# Filter.net
KiCad netlist of a schematic drawn in Altium Designer
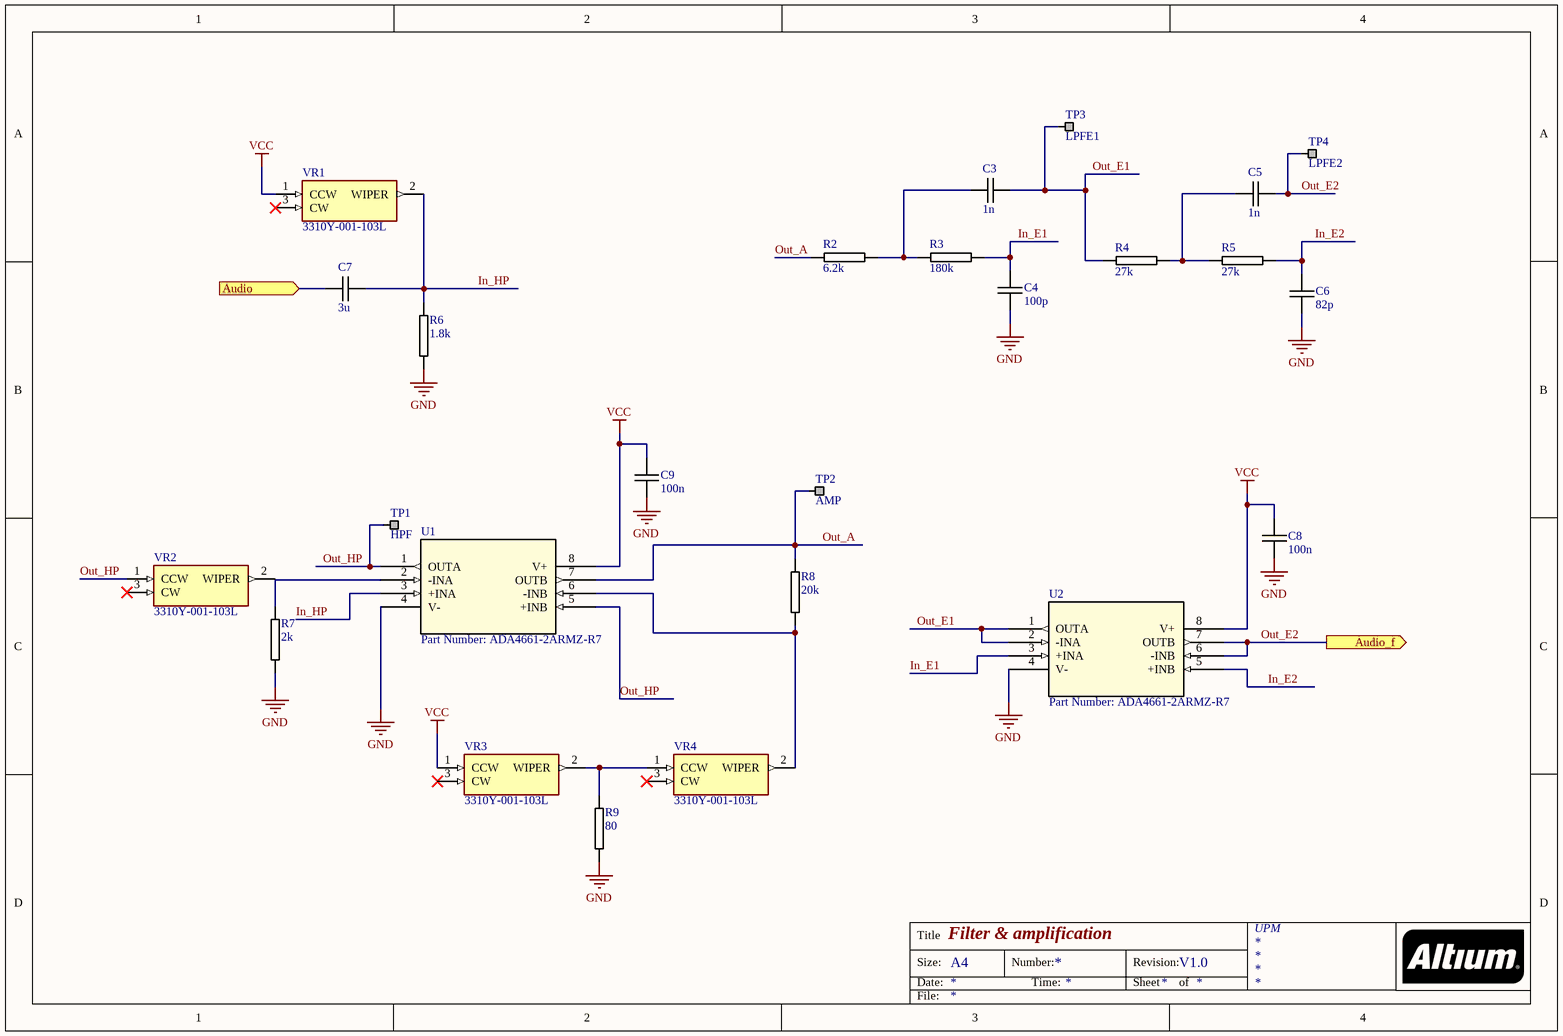
[diagram p0: Filter.SchDoc]

(export (version "E")
  (design (tool "Eeschema 10.0.6"))
  (components
    (comp (ref "C3")
      (value "1n")
      (footprint "0805C-GENERIC")
      (description "GENERIC CAPACITOR NON POLARISED0603")
      (libsource (lib "vh_altium_library") (part "C0805-GENERIC"))
    )
    (comp (ref "C4")
      (value "100p")
      (footprint "0805C-GENERIC")
      (description "GENERIC CAPACITOR NON POLARISED0603")
      (libsource (lib "vh_altium_library") (part "C0805-GENERIC"))
    )
    (comp (ref "C5")
      (value "1n")
      (footprint "0805C-GENERIC")
      (description "GENERIC CAPACITOR NON POLARISED0603")
      (libsource (lib "vh_altium_library") (part "C0805-GENERIC"))
    )
    (comp (ref "C6")
      (value "82p")
      (footprint "0805C-GENERIC")
      (description "GENERIC CAPACITOR NON POLARISED0603")
      (libsource (lib "vh_altium_library") (part "C0805-GENERIC"))
    )
    (comp (ref "C7")
      (value "3u")
      (footprint "0805C-GENERIC")
      (description "GENERIC CAPACITOR NON POLARISED0603")
      (libsource (lib "vh_altium_library") (part "C0805-GENERIC"))
    )
    (comp (ref "C8")
      (value "100n")
      (footprint "0805C-GENERIC")
      (description "GENERIC CAPACITOR NON POLARISED0603")
      (libsource (lib "vh_altium_library") (part "C0805-GENERIC"))
    )
    (comp (ref "C9")
      (value "100n")
      (footprint "0805C-GENERIC")
      (description "GENERIC CAPACITOR NON POLARISED0603")
      (libsource (lib "vh_altium_library") (part "C0805-GENERIC"))
    )
    (comp (ref "R2")
      (value "6.2k")
      (footprint "0805R-GENERIC")
      (description "GENERIC RESISTOR 0805")
      (libsource (lib "vh_altium_library") (part "R0805-GENERIC"))
    )
    (comp (ref "R3")
      (value "180k")
      (footprint "0805R-GENERIC")
      (description "GENERIC RESISTOR 0805")
      (libsource (lib "vh_altium_library") (part "R0805-GENERIC"))
    )
    (comp (ref "R4")
      (value "27k")
      (footprint "0805R-GENERIC")
      (description "GENERIC RESISTOR 0805")
      (libsource (lib "vh_altium_library") (part "R0805-GENERIC"))
    )
    (comp (ref "R5")
      (value "27k")
      (footprint "0805R-GENERIC")
      (description "GENERIC RESISTOR 0805")
      (libsource (lib "vh_altium_library") (part "R0805-GENERIC"))
    )
    (comp (ref "R6")
      (value "1.8k")
      (footprint "0805R-GENERIC")
      (description "GENERIC RESISTOR 0805")
      (libsource (lib "vh_altium_library") (part "R0805-GENERIC"))
    )
    (comp (ref "R7")
      (value "2k")
      (footprint "0805R-GENERIC")
      (description "GENERIC RESISTOR 0805")
      (libsource (lib "vh_altium_library") (part "R0805-GENERIC"))
    )
    (comp (ref "R8")
      (value "20k")
      (footprint "0805R-GENERIC")
      (description "GENERIC RESISTOR 0805")
      (libsource (lib "vh_altium_library") (part "R0805-GENERIC"))
    )
    (comp (ref "R9")
      (value "80")
      (footprint "0805R-GENERIC")
      (description "GENERIC RESISTOR 0805")
      (libsource (lib "vh_altium_library") (part "R0805-GENERIC"))
    )
    (comp (ref "TP1")
      (value "HPF")
      (footprint "TESTPIN")
      (description "TESTPIN SINGLE PIN HEADER")
      (libsource (lib "vh_altium_library") (part "TESTPIN"))
    )
    (comp (ref "TP2")
      (value "AMP")
      (footprint "TESTPIN")
      (description "TESTPIN SINGLE PIN HEADER")
      (libsource (lib "vh_altium_library") (part "TESTPIN"))
    )
    (comp (ref "TP3")
      (value "LPFE1")
      (footprint "TESTPIN")
      (description "TESTPIN SINGLE PIN HEADER")
      (libsource (lib "vh_altium_library") (part "TESTPIN"))
    )
    (comp (ref "TP4")
      (value "LPFE2")
      (footprint "TESTPIN")
      (description "TESTPIN SINGLE PIN HEADER")
      (libsource (lib "vh_altium_library") (part "TESTPIN"))
    )
    (comp (ref "U1")
      (value "Part Number: ADA4661-2ARMZ-R7")
      (footprint "RM_8")
      (description "No Description Available")
      (fields
        (field (name "MANUFACTURER_PART_NUMBER") "ADA4661-2ARMZ-R7")
        (field (name "COPYRIGHT") "Copyright (C) 2016 Accelerated Designs. All rights reserved")
      )
      (libsource (lib "2020-03-25_06-16-48") (part "ADA4661-2ARMZ-R7"))
    )
    (comp (ref "U2")
      (value "Part Number: ADA4661-2ARMZ-R7")
      (footprint "RM_8")
      (description "No Description Available")
      (fields
        (field (name "MANUFACTURER_PART_NUMBER") "ADA4661-2ARMZ-R7")
        (field (name "COPYRIGHT") "Copyright (C) 2016 Accelerated Designs. All rights reserved")
      )
      (libsource (lib "2020-03-25_06-16-48") (part "ADA4661-2ARMZ-R7"))
    )
    (comp (ref "VR1")
      (value "3310Y-001-103L")
      (footprint "3310Y-001")
      (description "Variable Resistor")
      (fields
        (field (name "MOUSER PART NUMBER") "652-3310Y-001-103L")
        (field (name "RS PART NUMBER") "5220625P")
      )
      (libsource (lib "PMOD") (part "3310Y-001-103L"))
    )
    (comp (ref "VR2")
      (value "3310Y-001-103L")
      (footprint "3310Y-001")
      (description "Variable Resistor")
      (fields
        (field (name "MOUSER PART NUMBER") "652-3310Y-001-103L")
        (field (name "RS PART NUMBER") "5220625P")
      )
      (libsource (lib "PMOD") (part "3310Y-001-103L"))
    )
    (comp (ref "VR3")
      (value "3310Y-001-103L")
      (footprint "3310Y-001")
      (description "Variable Resistor")
      (fields
        (field (name "MOUSER PART NUMBER") "652-3310Y-001-103L")
        (field (name "RS PART NUMBER") "5220625P")
      )
      (libsource (lib "PMOD") (part "3310Y-001-103L"))
    )
    (comp (ref "VR4")
      (value "3310Y-001-103L")
      (footprint "3310Y-001")
      (description "Variable Resistor")
      (fields
        (field (name "MOUSER PART NUMBER") "652-3310Y-001-103L")
        (field (name "RS PART NUMBER") "5220625P")
      )
      (libsource (lib "PMOD") (part "3310Y-001-103L"))
    )
  )
  (nets
    (net (code "1") (name "/Audio") (class "Default") (node (ref "C7") (pin "1") (pintype "passive")))
    (net (code "2") (name "/In_E1") (class "Default")
      (node (ref "C4") (pin "2") (pintype "passive"))
      (node (ref "R3") (pin "2") (pintype "passive"))
      (node (ref "U2") (pin "3") (pinfunction "+INA_3") (pintype "input"))
    )
    (net (code "3") (name "/In_E2") (class "Default")
      (node (ref "C6") (pin "2") (pintype "passive"))
      (node (ref "R5") (pin "2") (pintype "passive"))
      (node (ref "U2") (pin "5") (pinfunction "+INB_5") (pintype "input"))
    )
    (net (code "4") (name "/In_HP") (class "Default")
      (node (ref "C7") (pin "2") (pintype "passive"))
      (node (ref "R6") (pin "1") (pintype "passive"))
      (node (ref "U1") (pin "3") (pinfunction "+INA_3") (pintype "input"))
      (node (ref "VR1") (pin "2") (pinfunction "WIPER_2") (pintype "output"))
    )
    (net (code "5") (name "/Out_A") (class "Default")
      (node (ref "R2") (pin "1") (pintype "passive"))
      (node (ref "R8") (pin "1") (pintype "passive"))
      (node (ref "TP2") (pin "1") (pinfunction "1_1") (pintype "passive"))
      (node (ref "U1") (pin "7") (pinfunction "OUTB_7") (pintype "output"))
    )
    (net (code "6") (name "/Out_E1") (class "Default")
      (node (ref "C3") (pin "2") (pintype "passive"))
      (node (ref "R4") (pin "1") (pintype "passive"))
      (node (ref "TP3") (pin "1") (pinfunction "1_1") (pintype "passive"))
      (node (ref "U2") (pin "1") (pinfunction "OUTA_1") (pintype "output"))
      (node (ref "U2") (pin "2") (pinfunction "-INA_2") (pintype "input"))
    )
    (net (code "7") (name "/Out_E2") (class "Default")
      (node (ref "C5") (pin "2") (pintype "passive"))
      (node (ref "TP4") (pin "1") (pinfunction "1_1") (pintype "passive"))
      (node (ref "U2") (pin "6") (pinfunction "-INB_6") (pintype "input"))
      (node (ref "U2") (pin "7") (pinfunction "OUTB_7") (pintype "output"))
    )
    (net (code "8") (name "/Out_HP") (class "Default")
      (node (ref "TP1") (pin "1") (pinfunction "1_1") (pintype "passive"))
      (node (ref "U1") (pin "1") (pinfunction "OUTA_1") (pintype "output"))
      (node (ref "U1") (pin "5") (pinfunction "+INB_5") (pintype "input"))
      (node (ref "VR2") (pin "1") (pinfunction "CCW_1") (pintype "input"))
    )
    (net (code "9") (name "GND") (class "Default")
      (node (ref "C4") (pin "1") (pintype "passive"))
      (node (ref "C6") (pin "1") (pintype "passive"))
      (node (ref "C8") (pin "2") (pintype "passive"))
      (node (ref "C9") (pin "2") (pintype "passive"))
      (node (ref "R6") (pin "2") (pintype "passive"))
      (node (ref "R7") (pin "2") (pintype "passive"))
      (node (ref "R9") (pin "2") (pintype "passive"))
      (node (ref "U1") (pin "4") (pinfunction "V-_4") (pintype "power_in"))
      (node (ref "U2") (pin "4") (pinfunction "V-_4") (pintype "power_in"))
    )
    (net (code "10") (name "Net-(C3-Pad1)") (class "Default")
      (node (ref "C3") (pin "1") (pintype "passive"))
      (node (ref "R2") (pin "2") (pintype "passive"))
      (node (ref "R3") (pin "1") (pintype "passive"))
    )
    (net (code "11") (name "Net-(C5-Pad1)") (class "Default")
      (node (ref "C5") (pin "1") (pintype "passive"))
      (node (ref "R4") (pin "2") (pintype "passive"))
      (node (ref "R5") (pin "1") (pintype "passive"))
    )
    (net (code "12") (name "Net-(U1--INA)") (class "Default")
      (node (ref "R7") (pin "1") (pintype "passive"))
      (node (ref "U1") (pin "2") (pinfunction "-INA_2") (pintype "input"))
    )
    (net (code "13") (name "Net-(U1--INB)") (class "Default")
      (node (ref "R8") (pin "2") (pintype "passive"))
      (node (ref "U1") (pin "6") (pinfunction "-INB_6") (pintype "input"))
      (node (ref "VR4") (pin "2") (pinfunction "WIPER_2") (pintype "output"))
    )
    (net (code "14") (name "Net-(VR3-WIPER)") (class "Default")
      (node (ref "R9") (pin "1") (pintype "passive"))
      (node (ref "VR3") (pin "2") (pinfunction "WIPER_2") (pintype "output"))
      (node (ref "VR4") (pin "1") (pinfunction "CCW_1") (pintype "input"))
    )
    (net (code "15") (name "VCC") (class "Default")
      (node (ref "C8") (pin "1") (pintype "passive"))
      (node (ref "C9") (pin "1") (pintype "passive"))
      (node (ref "U1") (pin "8") (pinfunction "V+_8") (pintype "power_in"))
      (node (ref "U2") (pin "8") (pinfunction "V+_8") (pintype "power_in"))
      (node (ref "VR1") (pin "1") (pinfunction "CCW_1") (pintype "input"))
      (node (ref "VR3") (pin "1") (pinfunction "CCW_1") (pintype "input"))
    )
    (net (code "16") (name "unconnected-(VR1-CW-Pad3)") (class "Default")
      (node (ref "VR1") (pin "3") (pinfunction "CW_3") (pintype "input+no_connect"))
    )
    (net (code "17") (name "unconnected-(VR2-CW-Pad3)") (class "Default")
      (node (ref "VR2") (pin "3") (pinfunction "CW_3") (pintype "input+no_connect"))
    )
    (net (code "18") (name "unconnected-(VR2-WIPER-Pad2)") (class "Default")
      (node (ref "VR2") (pin "2") (pinfunction "WIPER_2") (pintype "output"))
    )
    (net (code "19") (name "unconnected-(VR3-CW-Pad3)") (class "Default")
      (node (ref "VR3") (pin "3") (pinfunction "CW_3") (pintype "input+no_connect"))
    )
    (net (code "20") (name "unconnected-(VR4-CW-Pad3)") (class "Default")
      (node (ref "VR4") (pin "3") (pinfunction "CW_3") (pintype "input+no_connect"))
    )
  )
)
